# FTDI.net
KiCad netlist of a schematic drawn in Altium Designer
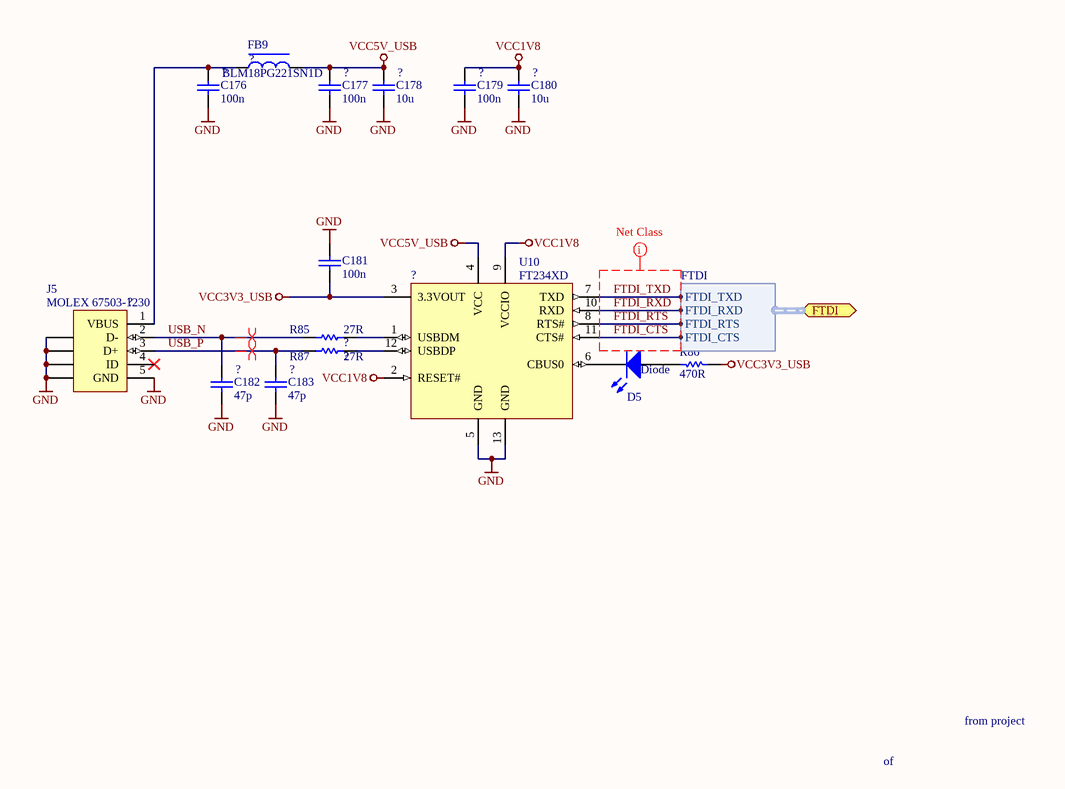
[diagram p0: FTDI.SchDoc]

(export (version "E")
  (design (tool "Eeschema 10.0.6"))
  (components
    (comp (ref "C176")
      (value "100n")
      (footprint "CAPC1005L")
      (description "Capacitor")
      (fields
        (field (name "MANUFACTURER") "Generic Components")
        (field (name "SN_CATEGORY") "?")
        (field (name "PUBLISHER") "Altium Hobart Technology Centre")
      )
      (libsource (lib "Miscellaneous Devices") (part "Cap"))
    )
    (comp (ref "C177")
      (value "100n")
      (footprint "CAPC1005L")
      (description "Capacitor")
      (fields
        (field (name "MANUFACTURER") "Generic Components")
        (field (name "SN_CATEGORY") "?")
        (field (name "PUBLISHER") "Altium Hobart Technology Centre")
      )
      (libsource (lib "Miscellaneous Devices") (part "Cap"))
    )
    (comp (ref "C178")
      (value "10u")
      (footprint "CAPC1005L")
      (description "Capacitor")
      (fields
        (field (name "MANUFACTURER") "Generic Components")
        (field (name "SN_CATEGORY") "?")
        (field (name "PUBLISHER") "Altium Hobart Technology Centre")
      )
      (libsource (lib "Miscellaneous Devices") (part "Cap"))
    )
    (comp (ref "C179")
      (value "100n")
      (footprint "CAPC1005L")
      (description "Capacitor")
      (fields
        (field (name "MANUFACTURER") "Generic Components")
        (field (name "SN_CATEGORY") "?")
        (field (name "PUBLISHER") "Altium Hobart Technology Centre")
      )
      (libsource (lib "Miscellaneous Devices") (part "Cap"))
    )
    (comp (ref "C180")
      (value "10u")
      (footprint "CAPC1005L")
      (description "Capacitor")
      (fields
        (field (name "MANUFACTURER") "Generic Components")
        (field (name "SN_CATEGORY") "?")
        (field (name "PUBLISHER") "Altium Hobart Technology Centre")
      )
      (libsource (lib "Miscellaneous Devices") (part "Cap"))
    )
    (comp (ref "C181")
      (value "100n")
      (footprint "CAPC1005L")
      (description "Capacitor")
      (fields
        (field (name "MANUFACTURER") "Generic Components")
        (field (name "PUBLISHER") "Altium Hobart Technology Centre")
      )
      (libsource (lib "Miscellaneous Devices") (part "Cap"))
    )
    (comp (ref "C182")
      (value "47p")
      (footprint "CAPC1005L")
      (description "Capacitor")
      (fields
        (field (name "MANUFACTURER") "Generic Components")
        (field (name "SN_CATEGORY") "?")
        (field (name "PUBLISHER") "Altium Hobart Technology Centre")
      )
      (libsource (lib "Miscellaneous Devices") (part "Cap"))
    )
    (comp (ref "C183")
      (value "47p")
      (footprint "CAPC1005L")
      (description "Capacitor")
      (fields
        (field (name "MANUFACTURER") "Generic Components")
        (field (name "SN_CATEGORY") "?")
        (field (name "PUBLISHER") "Altium Hobart Technology Centre")
      )
      (libsource (lib "Miscellaneous Devices") (part "Cap"))
    )
    (comp (ref "D5")
      (value "LED RED")
      (footprint "0603D")
      (description "Typical RED, GREEN, YELLOW, AMBER GaAs LED")
      (fields
        (field (name "MANUFACTURER") "Generic Components")
        (field (name "SN_CATEGORY") "Diode")
        (field (name "PUBLISHER") "Altium Hobart Technology Centre")
      )
      (libsource (lib "Miscellaneous Devices") (part "LED3"))
    )
    (comp (ref "FB9")
      (value "BLM18PG221SN1D")
      (footprint "INDC1608L")
      (description "Ferrite Bead")
      (fields (field (name "SN_CATEGORY") "?"))
      (libsource (lib "Schlib1") (part "INDUCTOR2"))
    )
    (comp (ref "J5")
      (value "MOLEX 67503-1230")
      (footprint "67503-1230")
      (fields (field (name "SN_CATEGORY") "?") (field (name "PUBLISHER") "Altium Limited"))
      (libsource (lib "TriggerCard") (part "mini_usb"))
    )
    (comp (ref "R85")
      (value "27R")
      (footprint "RESC1005L")
      (description "Resistor")
      (fields
        (field (name "MANUFACTURER") "Generic Components")
        (field (name "SN_CATEGORY") "?")
        (field (name "PUBLISHER") "Altium Hobart Technology Centre")
      )
      (libsource (lib "Miscellaneous Devices") (part "Res1"))
    )
    (comp (ref "R86")
      (value "470R")
      (footprint "RESC1005L")
      (description "Resistor")
      (fields
        (field (name "MANUFACTURER") "Generic Components")
        (field (name "SN_CATEGORY") "?")
        (field (name "PUBLISHER") "Altium Hobart Technology Centre")
      )
      (libsource (lib "Miscellaneous Devices") (part "Res1"))
    )
    (comp (ref "R87")
      (value "27R")
      (footprint "RESC1005L")
      (description "Resistor")
      (fields
        (field (name "MANUFACTURER") "Generic Components")
        (field (name "SN_CATEGORY") "?")
        (field (name "PUBLISHER") "Altium Hobart Technology Centre")
      )
      (libsource (lib "Miscellaneous Devices") (part "Res1"))
    )
    (comp (ref "U10")
      (value "FT234XD")
      (footprint "DFN-12_V")
      (description "FT234XD USB to BASIC UART IC, -40 to +85 degC, 12-Pin DFN, Pb-Free, Tray")
      (fields
        (field (name "MANUFACTURER") "FTDI")
        (field (name "PARTNUMBER") "FT234XD-T")
        (field (name "SN_CATEGORY") "?")
      )
      (libsource (lib "FTDI FT-X Series") (part "FT234XD-T"))
    )
  )
  (nets
    (net (code "2") (name "/FTDI_CTS") (class "Default")
      (node (ref "U10") (pin "11") (pinfunction "CTS#_11") (pintype "input"))
    )
    (net (code "3") (name "/FTDI_RTS") (class "Default")
      (node (ref "U10") (pin "8") (pinfunction "RTS#_8") (pintype "output"))
    )
    (net (code "4") (name "/FTDI_RXD") (class "Default")
      (node (ref "U10") (pin "10") (pinfunction "RXD_10") (pintype "input"))
    )
    (net (code "5") (name "/FTDI_TXD") (class "Default")
      (node (ref "U10") (pin "7") (pinfunction "TXD_7") (pintype "output"))
    )
    (net (code "6") (name "/USB_N") (class "Default")
      (node (ref "C182") (pin "1") (pinfunction "1_1") (pintype "passive"))
      (node (ref "J5") (pin "2") (pinfunction "D-_2") (pintype "bidirectional"))
      (node (ref "R85") (pin "2") (pinfunction "2_2") (pintype "passive"))
    )
    (net (code "7") (name "/USB_P") (class "Default")
      (node (ref "C183") (pin "1") (pinfunction "1_1") (pintype "passive"))
      (node (ref "J5") (pin "3") (pinfunction "D+_3") (pintype "bidirectional"))
      (node (ref "R87") (pin "2") (pinfunction "2_2") (pintype "passive"))
    )
    (net (code "9") (name "GND") (class "Default")
      (node (ref "C176") (pin "2") (pinfunction "2_2") (pintype "passive"))
      (node (ref "C177") (pin "2") (pinfunction "2_2") (pintype "passive"))
      (node (ref "C178") (pin "2") (pinfunction "2_2") (pintype "passive"))
      (node (ref "C179") (pin "2") (pinfunction "2_2") (pintype "passive"))
      (node (ref "C180") (pin "2") (pinfunction "2_2") (pintype "passive"))
      (node (ref "C181") (pin "1") (pinfunction "1_1") (pintype "passive"))
      (node (ref "C182") (pin "2") (pinfunction "2_2") (pintype "passive"))
      (node (ref "C183") (pin "2") (pinfunction "2_2") (pintype "passive"))
      (node (ref "J5") (pin "5") (pinfunction "GND_5") (pintype "power_in"))
      (node (ref "J5") (pin "MH1") (pinfunction "MH1_MH1") (pintype "passive"))
      (node (ref "J5") (pin "MH2") (pinfunction "MH2_MH2") (pintype "passive"))
      (node (ref "J5") (pin "MH3") (pinfunction "MH3_MH3") (pintype "passive"))
      (node (ref "J5") (pin "MH4") (pinfunction "MH4_MH4") (pintype "passive"))
      (node (ref "U10") (pin "13") (pinfunction "GND_13") (pintype "power_in"))
      (node (ref "U10") (pin "5") (pinfunction "GND_5") (pintype "power_in"))
    )
    (net (code "10") (name "Net-(D5-A)") (class "Default")
      (node (ref "D5") (pin "1") (pinfunction "A_1") (pintype "passive"))
      (node (ref "R86") (pin "2") (pinfunction "2_2") (pintype "passive"))
    )
    (net (code "11") (name "Net-(D5-K)") (class "Default")
      (node (ref "D5") (pin "2") (pinfunction "K_2") (pintype "passive"))
      (node (ref "U10") (pin "6") (pinfunction "CBUS0_6") (pintype "bidirectional"))
    )
    (net (code "12") (name "Net-(J5-VBUS)") (class "Default")
      (node (ref "C176") (pin "1") (pinfunction "1_1") (pintype "passive"))
      (node (ref "FB9") (pin "1") (pintype "passive"))
      (node (ref "J5") (pin "1") (pinfunction "VBUS_1") (pintype "power_in"))
    )
    (net (code "13") (name "Net-(U10-USBDM)") (class "Default")
      (node (ref "R85") (pin "1") (pinfunction "1_1") (pintype "passive"))
      (node (ref "U10") (pin "1") (pinfunction "USBDM_1") (pintype "bidirectional"))
    )
    (net (code "14") (name "Net-(U10-USBDP)") (class "Default")
      (node (ref "R87") (pin "1") (pinfunction "1_1") (pintype "passive"))
      (node (ref "U10") (pin "12") (pinfunction "USBDP_12") (pintype "bidirectional"))
    )
    (net (code "15") (name "VCC1V8") (class "Default")
      (node (ref "C179") (pin "1") (pinfunction "1_1") (pintype "passive"))
      (node (ref "C180") (pin "1") (pinfunction "1_1") (pintype "passive"))
      (node (ref "U10") (pin "2") (pinfunction "RESET#_2") (pintype "input"))
      (node (ref "U10") (pin "9") (pinfunction "VCCIO_9") (pintype "power_in"))
    )
    (net (code "16") (name "VCC3V3_USB") (class "Default")
      (node (ref "C181") (pin "2") (pinfunction "2_2") (pintype "passive"))
      (node (ref "R86") (pin "1") (pinfunction "1_1") (pintype "passive"))
      (node (ref "U10") (pin "3") (pinfunction "3.3VOUT_3") (pintype "power_in"))
    )
    (net (code "17") (name "VCC5V_USB") (class "Default")
      (node (ref "C177") (pin "1") (pinfunction "1_1") (pintype "passive"))
      (node (ref "C178") (pin "1") (pinfunction "1_1") (pintype "passive"))
      (node (ref "FB9") (pin "2") (pintype "passive"))
      (node (ref "U10") (pin "4") (pinfunction "VCC_4") (pintype "power_in"))
    )
    (net (code "18") (name "unconnected-(J5-ID-Pad4)") (class "Default")
      (node (ref "J5") (pin "4") (pinfunction "ID_4") (pintype "passive+no_connect"))
    )
  )
)
